# 1-Schematic_Pro_CTRL_2_Buck.net
KiCad netlist of a schematic drawn in EasyEDA
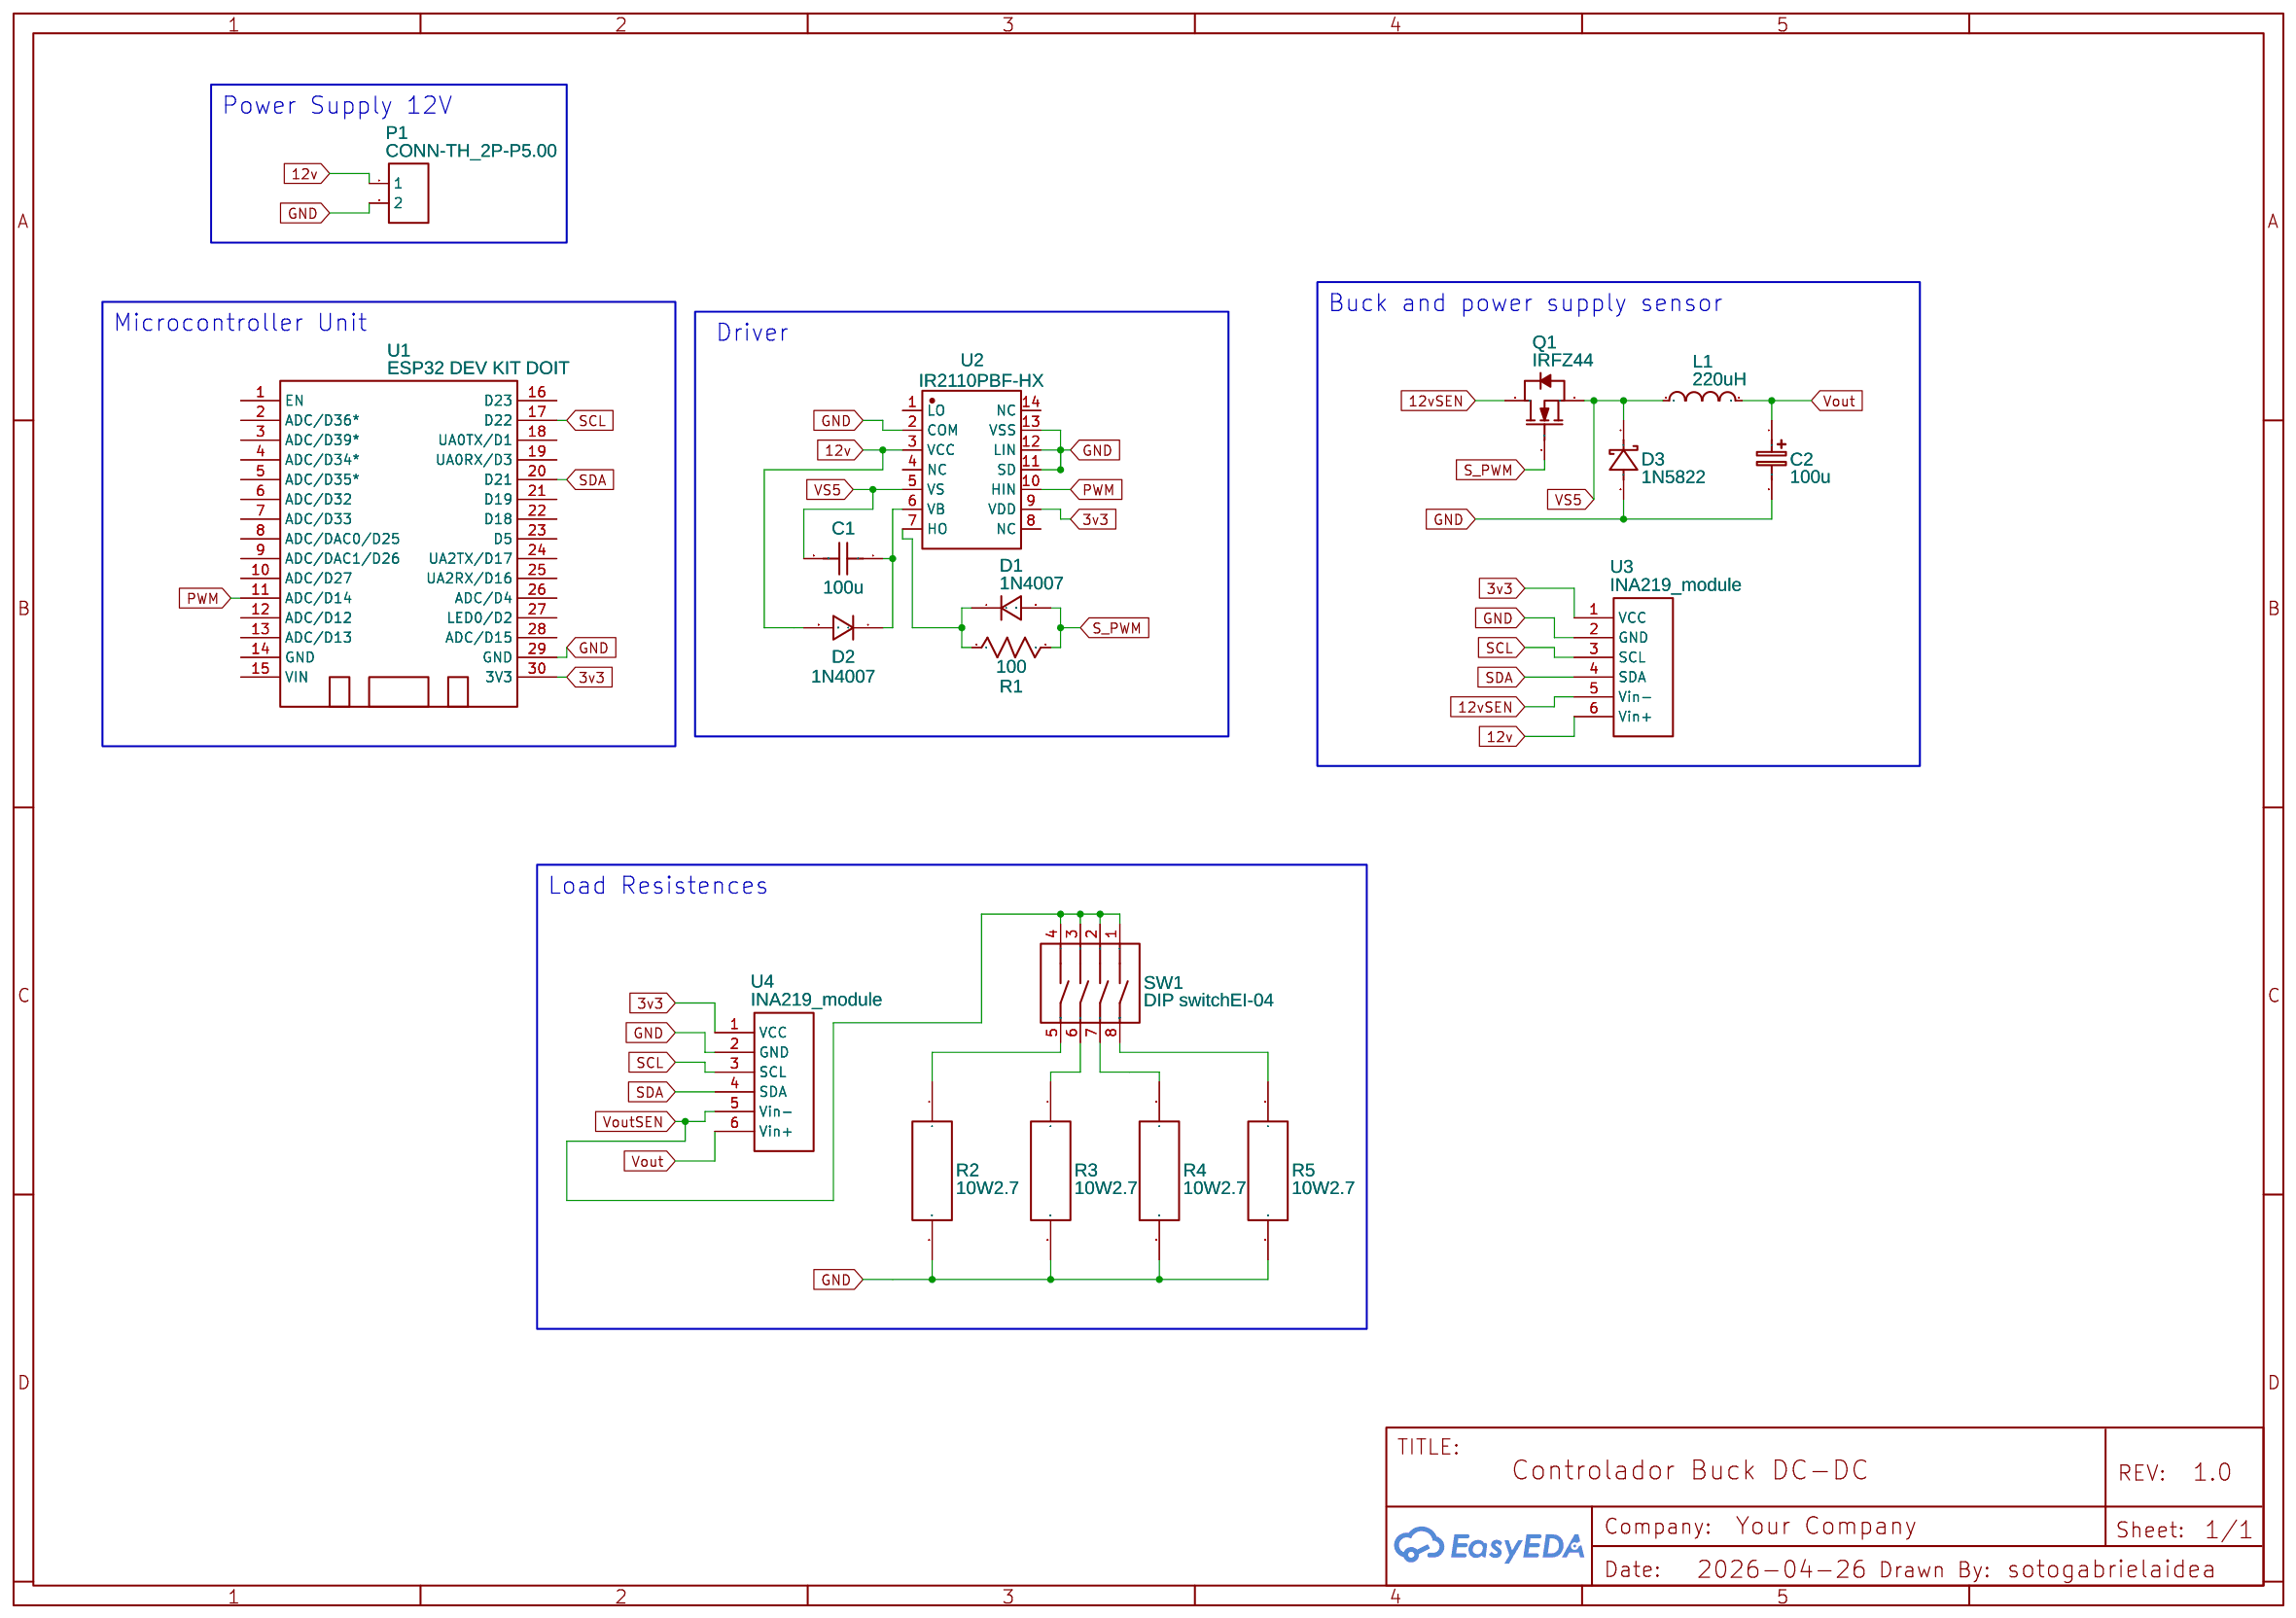
[diagram p0: schematic sheet]

(export (version "E")
  (design (tool "Eeschema 10.0.6"))
  (components
    (comp (ref "C1") (value "100u") (libsource (lib "") (part "C_RAD-0.1_US")))
    (comp (ref "C2") (value "100u") (libsource (lib "") (part "CE_TH_D10.0×F5.0_EU")))
    (comp (ref "D1")
      (value "1N4007")
      (fields (field (name "Manufacturer") "SEMTECH"))
      (libsource (lib "") (part "1N4007_1"))
    )
    (comp (ref "D2")
      (value "1N4007")
      (fields (field (name "Manufacturer") "SEMTECH"))
      (libsource (lib "") (part "1N4007"))
    )
    (comp (ref "D3")
      (value "1N5822")
      (fields (field (name "Manufacturer") "R+O(宏嘉诚)"))
      (libsource (lib "") (part "1N5822_C47345510"))
    )
    (comp (ref "L1")
      (value "220uH")
      (fields (field (name "Manufacturer Part") "TINDUCTOR-5MMX0.7"))
      (libsource (lib "") (part "TINDUCTOR-5MMX0.7"))
    )
    (comp (ref "P1") (value "CONN-TH_2P-P5.00") (libsource (lib "") (part "CONN-TH_2P-P5.00")))
    (comp (ref "Q1")
      (value "IRFZ44")
      (fields
        (field (name "Manufacturer Part") "HIRFZ44NPBF")
        (field (name "Manufacturer") "HXY MOSFET(华轩阳电子)")
      )
      (libsource (lib "") (part "HIRFZ44NPBF"))
    )
    (comp (ref "R1") (value "100") (libsource (lib "") (part "R_AXIAL-0.5_US")))
    (comp (ref "R2")
      (value "10W2.7")
      (fields (field (name "Manufacturer Part") "Yontex MKP 250V 6.8uF"))
      (libsource (lib "") (part "10W2.7"))
    )
    (comp (ref "R3")
      (value "10W2.7")
      (fields (field (name "Manufacturer Part") "Yontex MKP 250V 6.8uF"))
      (libsource (lib "") (part "10W2.7"))
    )
    (comp (ref "R4")
      (value "10W2.7")
      (fields (field (name "Manufacturer Part") "Yontex MKP 250V 6.8uF"))
      (libsource (lib "") (part "10W2.7"))
    )
    (comp (ref "R5")
      (value "10W2.7")
      (fields (field (name "Manufacturer Part") "Yontex MKP 250V 6.8uF"))
      (libsource (lib "") (part "10W2.7"))
    )
    (comp (ref "SW1")
      (value "DIP switchEI-04")
      (fields (field (name "Manufacturer Part") "拨码开关EI-04") (field (name "Manufacturer") "圜达"))
      (libsource (lib "") (part "DIP switchEI-04"))
    )
    (comp (ref "U1") (value "ESP32 DEV KIT DOIT") (libsource (lib "") (part "ESP32 DEV KIT DOIT")))
    (comp (ref "U2")
      (value "IR2110PBF-HX")
      (fields (field (name "Manufacturer") "ZHHXDZ(海芯电子)"))
      (libsource (lib "") (part "IR2110PBF-HX"))
    )
    (comp (ref "U3") (value "INA219_module") (libsource (lib "") (part "INA219_module")))
    (comp (ref "U4") (value "INA219_module") (libsource (lib "") (part "INA219_module")))
  )
  (nets
    (net (code "1") (name "3v3") (class "Default")
      (node (ref "U1") (pin "30") (pinfunction "3V3_30") (pintype "bidirectional"))
      (node (ref "U2") (pin "9") (pinfunction "VDD_9") (pintype "unspecified"))
      (node (ref "U3") (pin "1") (pinfunction "VCC_1") (pintype "unspecified"))
      (node (ref "U4") (pin "1") (pinfunction "VCC_1") (pintype "unspecified"))
    )
    (net (code "2") (name "12v") (class "Default")
      (node (ref "D2") (pin "2") (pinfunction "2_2") (pintype "unspecified"))
      (node (ref "P1") (pin "1") (pinfunction "1_1") (pintype "unspecified"))
      (node (ref "U2") (pin "3") (pinfunction "VCC_3") (pintype "unspecified"))
      (node (ref "U3") (pin "6") (pinfunction "Vin+_6") (pintype "unspecified"))
    )
    (net (code "3") (name "12vSEN") (class "Default")
      (node (ref "Q1") (pin "2") (pinfunction "D_2") (pintype "unspecified"))
      (node (ref "U3") (pin "5") (pinfunction "Vin-_5") (pintype "unspecified"))
    )
    (net (code "4") (name "GND") (class "Default")
      (node (ref "C2") (pin "2") (pinfunction "2_2") (pintype "unspecified"))
      (node (ref "D3") (pin "2") (pinfunction "A_2") (pintype "unspecified"))
      (node (ref "P1") (pin "2") (pinfunction "2_2") (pintype "unspecified"))
      (node (ref "R2") (pin "2") (pinfunction "2_2") (pintype "unspecified"))
      (node (ref "R3") (pin "2") (pinfunction "2_2") (pintype "unspecified"))
      (node (ref "R4") (pin "2") (pinfunction "2_2") (pintype "unspecified"))
      (node (ref "R5") (pin "2") (pinfunction "2_2") (pintype "unspecified"))
      (node (ref "U1") (pin "29") (pinfunction "GND_29") (pintype "bidirectional"))
      (node (ref "U2") (pin "11") (pinfunction "SD_11") (pintype "unspecified"))
      (node (ref "U2") (pin "12") (pinfunction "LIN_12") (pintype "unspecified"))
      (node (ref "U2") (pin "13") (pinfunction "VSS_13") (pintype "unspecified"))
      (node (ref "U2") (pin "2") (pinfunction "COM_2") (pintype "unspecified"))
      (node (ref "U3") (pin "2") (pinfunction "GND_2") (pintype "unspecified"))
      (node (ref "U4") (pin "2") (pinfunction "GND_2") (pintype "unspecified"))
    )
    (net (code "5") (name "Net-(R2-Pad1)") (class "Default")
      (node (ref "R2") (pin "1") (pinfunction "1_1") (pintype "unspecified"))
      (node (ref "SW1") (pin "5") (pinfunction "5_5") (pintype "unspecified"))
    )
    (net (code "6") (name "Net-(R3-Pad1)") (class "Default")
      (node (ref "R3") (pin "1") (pinfunction "1_1") (pintype "unspecified"))
      (node (ref "SW1") (pin "6") (pinfunction "6_6") (pintype "unspecified"))
    )
    (net (code "7") (name "Net-(R4-Pad1)") (class "Default")
      (node (ref "R4") (pin "1") (pinfunction "1_1") (pintype "unspecified"))
      (node (ref "SW1") (pin "7") (pinfunction "7_7") (pintype "unspecified"))
    )
    (net (code "8") (name "Net-(R5-Pad1)") (class "Default")
      (node (ref "R5") (pin "1") (pinfunction "1_1") (pintype "unspecified"))
      (node (ref "SW1") (pin "8") (pinfunction "8_8") (pintype "unspecified"))
    )
    (net (code "9") (name "Net-(U2-HO)") (class "Default")
      (node (ref "D1") (pin "1") (pinfunction "1_1") (pintype "unspecified"))
      (node (ref "R1") (pin "1") (pinfunction "1_1") (pintype "unspecified"))
      (node (ref "U2") (pin "7") (pinfunction "HO_7") (pintype "unspecified"))
    )
    (net (code "10") (name "Net-(U2-VB)") (class "Default")
      (node (ref "C1") (pin "1") (pinfunction "1_1") (pintype "unspecified"))
      (node (ref "D2") (pin "1") (pinfunction "1_1") (pintype "unspecified"))
      (node (ref "U2") (pin "6") (pinfunction "VB_6") (pintype "unspecified"))
    )
    (net (code "11") (name "PWM") (class "Default")
      (node (ref "U1") (pin "11") (pinfunction "ADC/D14_11") (pintype "bidirectional"))
      (node (ref "U2") (pin "10") (pinfunction "HIN_10") (pintype "unspecified"))
    )
    (net (code "12") (name "SCL") (class "Default")
      (node (ref "U1") (pin "17") (pinfunction "D22_17") (pintype "bidirectional"))
      (node (ref "U3") (pin "3") (pinfunction "SCL_3") (pintype "unspecified"))
      (node (ref "U4") (pin "3") (pinfunction "SCL_3") (pintype "unspecified"))
    )
    (net (code "13") (name "SDA") (class "Default")
      (node (ref "U1") (pin "20") (pinfunction "D21_20") (pintype "bidirectional"))
      (node (ref "U3") (pin "4") (pinfunction "SDA_4") (pintype "unspecified"))
      (node (ref "U4") (pin "4") (pinfunction "SDA_4") (pintype "unspecified"))
    )
    (net (code "14") (name "S_PWM") (class "Default")
      (node (ref "D1") (pin "2") (pinfunction "2_2") (pintype "unspecified"))
      (node (ref "Q1") (pin "1") (pinfunction "G_1") (pintype "unspecified"))
      (node (ref "R1") (pin "2") (pinfunction "2_2") (pintype "unspecified"))
    )
    (net (code "15") (name "VS5") (class "Default")
      (node (ref "C1") (pin "2") (pinfunction "2_2") (pintype "unspecified"))
      (node (ref "D3") (pin "1") (pinfunction "K_1") (pintype "unspecified"))
      (node (ref "L1") (pin "1") (pinfunction "1_1") (pintype "unspecified"))
      (node (ref "Q1") (pin "3") (pinfunction "S_3") (pintype "unspecified"))
      (node (ref "U2") (pin "5") (pinfunction "VS_5") (pintype "unspecified"))
    )
    (net (code "16") (name "Vout") (class "Default")
      (node (ref "C2") (pin "1") (pinfunction "1_1") (pintype "unspecified"))
      (node (ref "L1") (pin "2") (pinfunction "2_2") (pintype "unspecified"))
      (node (ref "U4") (pin "6") (pinfunction "Vin+_6") (pintype "unspecified"))
    )
    (net (code "17") (name "VoutSEN") (class "Default")
      (node (ref "SW1") (pin "1") (pinfunction "1_1") (pintype "unspecified"))
      (node (ref "SW1") (pin "2") (pinfunction "2_2") (pintype "unspecified"))
      (node (ref "SW1") (pin "3") (pinfunction "3_3") (pintype "unspecified"))
      (node (ref "SW1") (pin "4") (pinfunction "4_4") (pintype "unspecified"))
      (node (ref "U4") (pin "5") (pinfunction "Vin-_5") (pintype "unspecified"))
    )
    (net (code "18") (name "unconnected-(U1-ADC{slash}D4-Pad26)") (class "Default")
      (node (ref "U1") (pin "26") (pinfunction "ADC/D4_26") (pintype "bidirectional"))
    )
    (net (code "19") (name "unconnected-(U1-ADC{slash}D12-Pad12)") (class "Default")
      (node (ref "U1") (pin "12") (pinfunction "ADC/D12_12") (pintype "bidirectional"))
    )
    (net (code "20") (name "unconnected-(U1-ADC{slash}D13-Pad13)") (class "Default")
      (node (ref "U1") (pin "13") (pinfunction "ADC/D13_13") (pintype "bidirectional"))
    )
    (net (code "21") (name "unconnected-(U1-ADC{slash}D15-Pad28)") (class "Default")
      (node (ref "U1") (pin "28") (pinfunction "ADC/D15_28") (pintype "bidirectional"))
    )
    (net (code "22") (name "unconnected-(U1-ADC{slash}D27-Pad10)") (class "Default")
      (node (ref "U1") (pin "10") (pinfunction "ADC/D27_10") (pintype "bidirectional"))
    )
    (net (code "23") (name "unconnected-(U1-ADC{slash}D32-Pad6)") (class "Default")
      (node (ref "U1") (pin "6") (pinfunction "ADC/D32_6") (pintype "bidirectional"))
    )
    (net (code "24") (name "unconnected-(U1-ADC{slash}D33-Pad7)") (class "Default")
      (node (ref "U1") (pin "7") (pinfunction "ADC/D33_7") (pintype "bidirectional"))
    )
    (net (code "25") (name "unconnected-(U1-ADC{slash}D34*-Pad4)") (class "Default")
      (node (ref "U1") (pin "4") (pinfunction "ADC/D34*_4") (pintype "input"))
    )
    (net (code "26") (name "unconnected-(U1-ADC{slash}D35*-Pad5)") (class "Default")
      (node (ref "U1") (pin "5") (pinfunction "ADC/D35*_5") (pintype "input"))
    )
    (net (code "27") (name "unconnected-(U1-ADC{slash}D36*-Pad2)") (class "Default")
      (node (ref "U1") (pin "2") (pinfunction "ADC/D36*_2") (pintype "input"))
    )
    (net (code "28") (name "unconnected-(U1-ADC{slash}D39*-Pad3)") (class "Default")
      (node (ref "U1") (pin "3") (pinfunction "ADC/D39*_3") (pintype "input"))
    )
    (net (code "29") (name "unconnected-(U1-ADC{slash}DAC0{slash}D25-Pad8)") (class "Default")
      (node (ref "U1") (pin "8") (pinfunction "ADC/DAC0/D25_8") (pintype "bidirectional"))
    )
    (net (code "30") (name "unconnected-(U1-ADC{slash}DAC1{slash}D26-Pad9)") (class "Default")
      (node (ref "U1") (pin "9") (pinfunction "ADC/DAC1/D26_9") (pintype "bidirectional"))
    )
    (net (code "31") (name "unconnected-(U1-D5-Pad23)") (class "Default")
      (node (ref "U1") (pin "23") (pinfunction "D5_23") (pintype "bidirectional"))
    )
    (net (code "32") (name "unconnected-(U1-D18-Pad22)") (class "Default")
      (node (ref "U1") (pin "22") (pinfunction "D18_22") (pintype "bidirectional"))
    )
    (net (code "33") (name "unconnected-(U1-D19-Pad21)") (class "Default")
      (node (ref "U1") (pin "21") (pinfunction "D19_21") (pintype "bidirectional"))
    )
    (net (code "34") (name "unconnected-(U1-D23-Pad16)") (class "Default")
      (node (ref "U1") (pin "16") (pinfunction "D23_16") (pintype "bidirectional"))
    )
    (net (code "35") (name "unconnected-(U1-EN-Pad1)") (class "Default")
      (node (ref "U1") (pin "1") (pinfunction "EN_1") (pintype "bidirectional"))
    )
    (net (code "36") (name "unconnected-(U1-GND-Pad14)") (class "Default")
      (node (ref "U1") (pin "14") (pinfunction "GND_14") (pintype "bidirectional"))
    )
    (net (code "37") (name "unconnected-(U1-LED0{slash}D2-Pad27)") (class "Default")
      (node (ref "U1") (pin "27") (pinfunction "LED0/D2_27") (pintype "bidirectional"))
    )
    (net (code "38") (name "unconnected-(U1-UA0RX{slash}D3-Pad19)") (class "Default")
      (node (ref "U1") (pin "19") (pinfunction "UA0RX/D3_19") (pintype "bidirectional"))
    )
    (net (code "39") (name "unconnected-(U1-UA0TX{slash}D1-Pad18)") (class "Default")
      (node (ref "U1") (pin "18") (pinfunction "UA0TX/D1_18") (pintype "bidirectional"))
    )
    (net (code "40") (name "unconnected-(U1-UA2RX{slash}D16-Pad25)") (class "Default")
      (node (ref "U1") (pin "25") (pinfunction "UA2RX/D16_25") (pintype "bidirectional"))
    )
    (net (code "41") (name "unconnected-(U1-UA2TX{slash}D17-Pad24)") (class "Default")
      (node (ref "U1") (pin "24") (pinfunction "UA2TX/D17_24") (pintype "bidirectional"))
    )
    (net (code "42") (name "unconnected-(U1-VIN-Pad15)") (class "Default")
      (node (ref "U1") (pin "15") (pinfunction "VIN_15") (pintype "input"))
    )
    (net (code "43") (name "unconnected-(U2-LO-Pad1)") (class "Default")
      (node (ref "U2") (pin "1") (pinfunction "LO_1") (pintype "unspecified"))
    )
    (net (code "44") (name "unconnected-(U2-NC-Pad4)") (class "Default")
      (node (ref "U2") (pin "4") (pinfunction "NC_4") (pintype "unspecified"))
    )
    (net (code "45") (name "unconnected-(U2-NC-Pad8)") (class "Default")
      (node (ref "U2") (pin "8") (pinfunction "NC_8") (pintype "unspecified"))
    )
    (net (code "46") (name "unconnected-(U2-NC-Pad14)") (class "Default")
      (node (ref "U2") (pin "14") (pinfunction "NC_14") (pintype "unspecified"))
    )
  )
)
